# shiftregisters.net
KiCad netlist of a schematic drawn in EAGLE
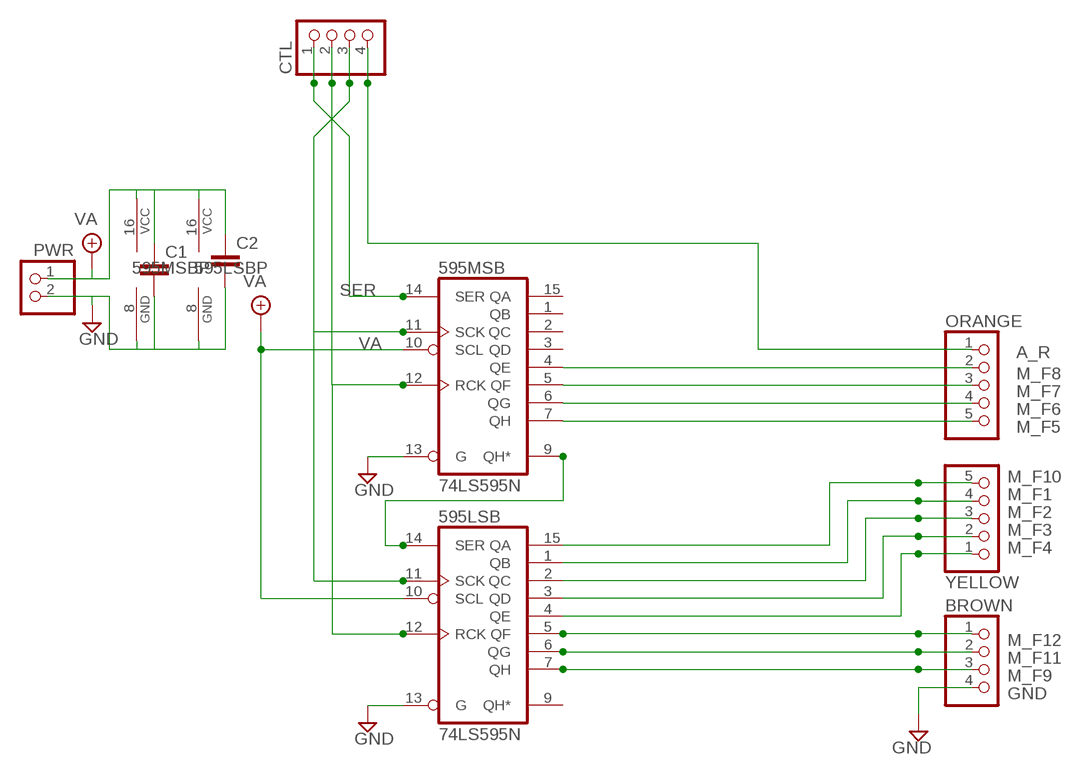
[diagram p0: schematic, sheet 1]

(export (version "E")
  (design (tool "Eeschema 10.0.6"))
  (components
    (comp (ref "595LSB")
      (value "74LS595N")
      (footprint "eagle-import:DIL16")
      (libsource (lib "eagle-import") (part "74595NLS"))
    )
    (comp (ref "595MSB")
      (value "74LS595N")
      (footprint "eagle-import:DIL16")
      (libsource (lib "eagle-import") (part "74595NLS"))
    )
    (comp (ref "BROWN")
      (value "PINHD-1X4")
      (footprint "eagle-import:1X04")
      (libsource (lib "eagle-import") (part "PINHD-1X4"))
    )
    (comp (ref "C1")
      (value "050X030_0251")
      (footprint "eagle-import:050X030_025")
      (libsource (lib "eagle-import") (part "050X030_0251"))
    )
    (comp (ref "C2")
      (value "050X030_0251")
      (footprint "eagle-import:050X030_025")
      (libsource (lib "eagle-import") (part "050X030_0251"))
    )
    (comp (ref "CTL")
      (value "PINHD-1X4")
      (footprint "eagle-import:1X04")
      (libsource (lib "eagle-import") (part "PINHD-1X4"))
    )
    (comp (ref "ORANGE")
      (value "PINHD-1X5")
      (footprint "eagle-import:1X05")
      (libsource (lib "eagle-import") (part "PINHD-1X5"))
    )
    (comp (ref "PWR")
      (value "PINHD-1X2")
      (footprint "eagle-import:1X02")
      (libsource (lib "eagle-import") (part "PINHD-1X2"))
    )
    (comp (ref "YELLOW")
      (value "PINHD-1X5")
      (footprint "eagle-import:1X05")
      (libsource (lib "eagle-import") (part "PINHD-1X5"))
    )
  )
  (nets
    (net (code "1") (name "/M_F1") (class "Default")
      (node (ref "595LSB") (pin "1") (pinfunction "QB_1") (pintype "tri_state"))
      (node (ref "YELLOW") (pin "4") (pinfunction "4_4") (pintype "passive"))
    )
    (net (code "2") (name "/M_F2") (class "Default")
      (node (ref "595LSB") (pin "2") (pinfunction "QC_2") (pintype "tri_state"))
      (node (ref "YELLOW") (pin "3") (pinfunction "3_3") (pintype "passive"))
    )
    (net (code "3") (name "/M_F3") (class "Default")
      (node (ref "595LSB") (pin "3") (pinfunction "QD_3") (pintype "tri_state"))
      (node (ref "YELLOW") (pin "2") (pinfunction "2_2") (pintype "passive"))
    )
    (net (code "4") (name "/M_F4") (class "Default")
      (node (ref "595LSB") (pin "4") (pinfunction "QE_4") (pintype "tri_state"))
      (node (ref "YELLOW") (pin "1") (pinfunction "1_1") (pintype "passive"))
    )
    (net (code "5") (name "/M_F5") (class "Default")
      (node (ref "595MSB") (pin "7") (pinfunction "QH_7") (pintype "tri_state"))
      (node (ref "ORANGE") (pin "5") (pinfunction "5_5") (pintype "passive"))
    )
    (net (code "6") (name "/M_F6") (class "Default")
      (node (ref "595MSB") (pin "6") (pinfunction "QG_6") (pintype "tri_state"))
      (node (ref "ORANGE") (pin "4") (pinfunction "4_4") (pintype "passive"))
    )
    (net (code "7") (name "/M_F7") (class "Default")
      (node (ref "595MSB") (pin "5") (pinfunction "QF_5") (pintype "tri_state"))
      (node (ref "ORANGE") (pin "3") (pinfunction "3_3") (pintype "passive"))
    )
    (net (code "8") (name "/M_F8") (class "Default")
      (node (ref "595MSB") (pin "4") (pinfunction "QE_4") (pintype "tri_state"))
      (node (ref "ORANGE") (pin "2") (pinfunction "2_2") (pintype "passive"))
    )
    (net (code "9") (name "/M_F9") (class "Default")
      (node (ref "595LSB") (pin "7") (pinfunction "QH_7") (pintype "tri_state"))
      (node (ref "BROWN") (pin "3") (pinfunction "3_3") (pintype "passive"))
    )
    (net (code "10") (name "/M_F10") (class "Default")
      (node (ref "595LSB") (pin "15") (pinfunction "QA_15") (pintype "tri_state"))
      (node (ref "YELLOW") (pin "5") (pinfunction "5_5") (pintype "passive"))
    )
    (net (code "11") (name "/M_F11") (class "Default")
      (node (ref "595LSB") (pin "6") (pinfunction "QG_6") (pintype "tri_state"))
      (node (ref "BROWN") (pin "2") (pinfunction "2_2") (pintype "passive"))
    )
    (net (code "12") (name "/M_F12") (class "Default")
      (node (ref "595LSB") (pin "5") (pinfunction "QF_5") (pintype "tri_state"))
      (node (ref "BROWN") (pin "1") (pinfunction "1_1") (pintype "passive"))
    )
    (net (code "13") (name "/SER") (class "Default")
      (node (ref "595MSB") (pin "14") (pinfunction "SER_14") (pintype "input"))
      (node (ref "CTL") (pin "1") (pinfunction "1_1") (pintype "passive"))
    )
    (net (code "14") (name "GND") (class "Default")
      (node (ref "595LSB") (pin "13") (pinfunction "G_13") (pintype "input"))
      (node (ref "595LSB") (pin "8") (pinfunction "GND_8") (pintype "power_in"))
      (node (ref "595MSB") (pin "13") (pinfunction "G_13") (pintype "input"))
      (node (ref "595MSB") (pin "8") (pinfunction "GND_8") (pintype "power_in"))
      (node (ref "BROWN") (pin "4") (pinfunction "4_4") (pintype "passive"))
      (node (ref "C1") (pin "2") (pinfunction "2_2") (pintype "passive"))
      (node (ref "C2") (pin "2") (pinfunction "2_2") (pintype "passive"))
      (node (ref "PWR") (pin "2") (pinfunction "2_2") (pintype "passive"))
    )
    (net (code "15") (name "Net-(595LSBA-RCK)") (class "Default")
      (node (ref "595LSB") (pin "12") (pinfunction "RCK_12") (pintype "input"))
      (node (ref "595MSB") (pin "12") (pinfunction "RCK_12") (pintype "input"))
      (node (ref "CTL") (pin "2") (pinfunction "2_2") (pintype "passive"))
    )
    (net (code "16") (name "Net-(595LSBA-SCK)") (class "Default")
      (node (ref "595LSB") (pin "11") (pinfunction "SCK_11") (pintype "input"))
      (node (ref "595MSB") (pin "11") (pinfunction "SCK_11") (pintype "input"))
      (node (ref "CTL") (pin "3") (pinfunction "3_3") (pintype "passive"))
    )
    (net (code "17") (name "Net-(595LSBA-SER)") (class "Default")
      (node (ref "595LSB") (pin "14") (pinfunction "SER_14") (pintype "input"))
      (node (ref "595MSB") (pin "9") (pinfunction "QH*_9") (pintype "tri_state"))
    )
    (net (code "18") (name "Net-(CTL-Pad4)") (class "Default")
      (node (ref "CTL") (pin "4") (pinfunction "4_4") (pintype "passive"))
      (node (ref "ORANGE") (pin "1") (pinfunction "1_1") (pintype "passive"))
    )
    (net (code "19") (name "VA") (class "Default")
      (node (ref "595LSB") (pin "10") (pinfunction "SCL_10") (pintype "input"))
      (node (ref "595LSB") (pin "16") (pinfunction "VCC_16") (pintype "power_in"))
      (node (ref "595MSB") (pin "10") (pinfunction "SCL_10") (pintype "input"))
      (node (ref "595MSB") (pin "16") (pinfunction "VCC_16") (pintype "power_in"))
      (node (ref "C1") (pin "1") (pinfunction "1_1") (pintype "passive"))
      (node (ref "C2") (pin "1") (pinfunction "1_1") (pintype "passive"))
      (node (ref "PWR") (pin "1") (pinfunction "1_1") (pintype "passive"))
    )
    (net (code "20") (name "unconnected-(595LSBA-QH*-Pad9)") (class "Default")
      (node (ref "595LSB") (pin "9") (pinfunction "QH*_9") (pintype "tri_state"))
    )
    (net (code "21") (name "unconnected-(595MSBA-QA-Pad15)") (class "Default")
      (node (ref "595MSB") (pin "15") (pinfunction "QA_15") (pintype "tri_state"))
    )
    (net (code "22") (name "unconnected-(595MSBA-QB-Pad1)") (class "Default")
      (node (ref "595MSB") (pin "1") (pinfunction "QB_1") (pintype "tri_state"))
    )
    (net (code "23") (name "unconnected-(595MSBA-QC-Pad2)") (class "Default")
      (node (ref "595MSB") (pin "2") (pinfunction "QC_2") (pintype "tri_state"))
    )
    (net (code "24") (name "unconnected-(595MSBA-QD-Pad3)") (class "Default")
      (node (ref "595MSB") (pin "3") (pinfunction "QD_3") (pintype "tri_state"))
    )
  )
)
